# uc3906_charger_2.net
KiCad netlist of a schematic drawn in EAGLE
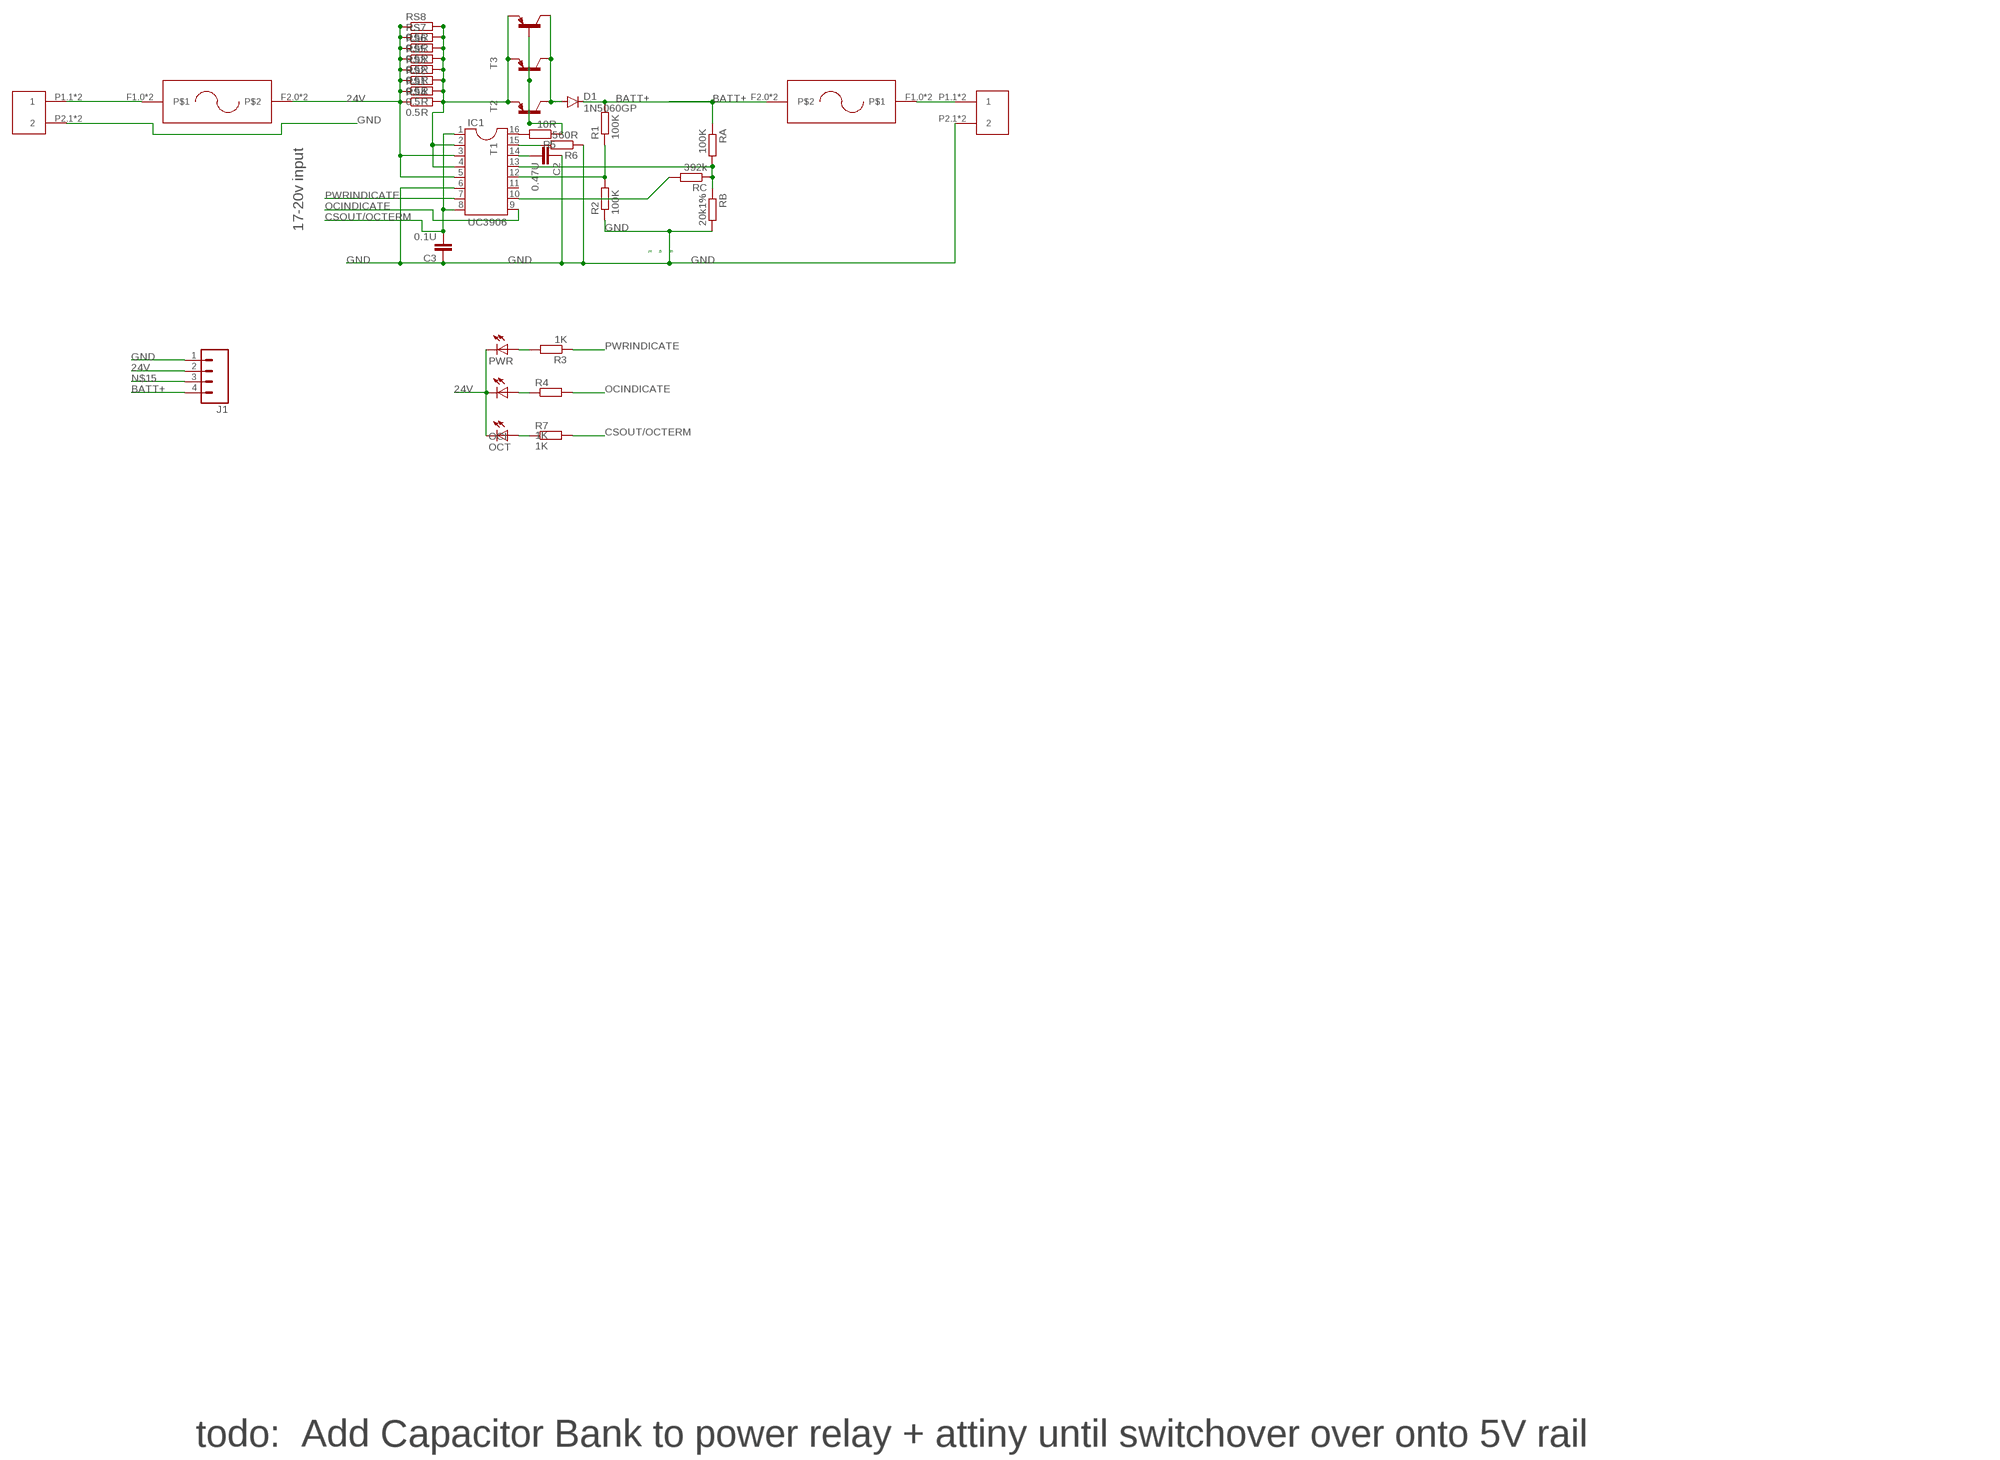
[diagram p0: schematic, sheet 1]

(export (version "E")
  (design (tool "Eeschema 10.0.6"))
  (components
    (comp (ref "BATT")
      (value "BARRIERTERMINAL")
      (footprint "eagle-import:BARRIERTERMINAL")
      (libsource (lib "eagle-import") (part "BARRIERTERMINAL"))
    )
    (comp (ref "C2")
      (value "0.47U")
      (footprint "eagle-import:C050-024X044")
      (libsource (lib "eagle-import") (part "C-EU050-024X044"))
    )
    (comp (ref "C3")
      (value "0.1U")
      (footprint "eagle-import:C050-024X044")
      (libsource (lib "eagle-import") (part "C-EU050-024X044"))
    )
    (comp (ref "D1")
      (value "1N5060GP")
      (footprint "eagle-import:DO15-12")
      (libsource (lib "eagle-import") (part "1N5060GP"))
    )
    (comp (ref "IC1")
      (value "UC3906")
      (footprint "eagle-import:DIL16")
      (libsource (lib "eagle-import") (part "DIL16"))
    )
    (comp (ref "J1")
      (value "CONN_04LONGPADS")
      (footprint "eagle-import:1X04_LONGPADS")
      (libsource (lib "eagle-import") (part "CONN_04LONGPADS"))
    )
    (comp (ref "OCI")
      (value "LED5MM")
      (footprint "eagle-import:LED5MM")
      (libsource (lib "eagle-import") (part "LED5MM"))
    )
    (comp (ref "OCT")
      (value "LED5MM")
      (footprint "eagle-import:LED5MM")
      (libsource (lib "eagle-import") (part "LED5MM"))
    )
    (comp (ref "POWERIN")
      (value "BARRIERTERMINAL")
      (footprint "eagle-import:BARRIERTERMINAL")
      (libsource (lib "eagle-import") (part "BARRIERTERMINAL"))
    )
    (comp (ref "PWR")
      (value "LED5MM")
      (footprint "eagle-import:LED5MM")
      (libsource (lib "eagle-import") (part "LED5MM"))
    )
    (comp (ref "R1")
      (value "100K")
      (footprint "eagle-import:0204_7")
      (libsource (lib "eagle-import") (part "R-EU_0204/7"))
    )
    (comp (ref "R2")
      (value "100K")
      (footprint "eagle-import:0204_7")
      (libsource (lib "eagle-import") (part "R-EU_0204/7"))
    )
    (comp (ref "R3")
      (value "1K")
      (footprint "eagle-import:0204_7")
      (libsource (lib "eagle-import") (part "R-EU_0204/7"))
    )
    (comp (ref "R4")
      (value "1K")
      (footprint "eagle-import:0204_7")
      (libsource (lib "eagle-import") (part "R-EU_0204/7"))
    )
    (comp (ref "R5")
      (value "10R")
      (footprint "eagle-import:0204_7")
      (libsource (lib "eagle-import") (part "R-EU_0204/7"))
    )
    (comp (ref "R6")
      (value "560R")
      (footprint "eagle-import:0204_7")
      (libsource (lib "eagle-import") (part "R-EU_0204/7"))
    )
    (comp (ref "R7")
      (value "1K")
      (footprint "eagle-import:0204_7")
      (libsource (lib "eagle-import") (part "R-EU_0204/7"))
    )
    (comp (ref "RA")
      (value "100K")
      (footprint "eagle-import:0204_7")
      (libsource (lib "eagle-import") (part "R-EU_0204/7"))
    )
    (comp (ref "RB")
      (value "20k1%")
      (footprint "eagle-import:0204_7")
      (libsource (lib "eagle-import") (part "R-EU_0204/7"))
    )
    (comp (ref "RC")
      (value "392k")
      (footprint "eagle-import:0204_7")
      (libsource (lib "eagle-import") (part "R-EU_0204/7"))
    )
    (comp (ref "RS1")
      (value "0.5R")
      (footprint "eagle-import:0411_15")
      (libsource (lib "eagle-import") (part "resistor_R-EU_0411/15"))
    )
    (comp (ref "RS2")
      (value "0.5R")
      (footprint "eagle-import:0411_15")
      (libsource (lib "eagle-import") (part "resistor_R-EU_0411/15"))
    )
    (comp (ref "RS3")
      (value "0.5R")
      (footprint "eagle-import:0411_15")
      (libsource (lib "eagle-import") (part "resistor_R-EU_0411/15"))
    )
    (comp (ref "RS4")
      (value "0.5R")
      (footprint "eagle-import:0411_15")
      (libsource (lib "eagle-import") (part "resistor_R-EU_0411/15"))
    )
    (comp (ref "RS5")
      (value "0.5R")
      (footprint "eagle-import:0411_15")
      (libsource (lib "eagle-import") (part "resistor_R-EU_0411/15"))
    )
    (comp (ref "RS6")
      (value "0.5R")
      (footprint "eagle-import:0411_15")
      (libsource (lib "eagle-import") (part "resistor_R-EU_0411/15"))
    )
    (comp (ref "RS7")
      (value "0.5R")
      (footprint "eagle-import:0411_15")
      (libsource (lib "eagle-import") (part "resistor_R-EU_0411/15"))
    )
    (comp (ref "RS8")
      (value "0.5R")
      (footprint "eagle-import:0411_15")
      (libsource (lib "eagle-import") (part "resistor_R-EU_0411/15"))
    )
    (comp (ref "T1")
      (value "TIP32C")
      (footprint "eagle-import:TO220")
      (libsource (lib "eagle-import") (part "TIP32C"))
    )
    (comp (ref "T2")
      (value "TIP32C")
      (footprint "eagle-import:TO220")
      (libsource (lib "eagle-import") (part "TIP32C"))
    )
    (comp (ref "T3")
      (value "TIP32C")
      (footprint "eagle-import:TO220")
      (libsource (lib "eagle-import") (part "TIP32C"))
    )
    (comp (ref "U$1")
      (value "18MMFUSEHOLDER")
      (footprint "eagle-import:18MMFUSEHOLDER")
      (libsource (lib "eagle-import") (part "18MMFUSEHOLDER"))
    )
    (comp (ref "U$2")
      (value "18MMFUSEHOLDER")
      (footprint "eagle-import:18MMFUSEHOLDER")
      (libsource (lib "eagle-import") (part "18MMFUSEHOLDER"))
    )
  )
  (nets
    (net (code "1") (name "/24V") (class "Default")
      (node (ref "IC1") (pin "3") (pinfunction "3_3") (pintype "passive"))
      (node (ref "IC1") (pin "5") (pinfunction "5_5") (pintype "passive"))
      (node (ref "J1") (pin "2") (pinfunction "2_2") (pintype "passive"))
      (node (ref "OCI") (pin "K") (pinfunction "C_K") (pintype "passive"))
      (node (ref "OCT") (pin "K") (pinfunction "C_K") (pintype "passive"))
      (node (ref "PWR") (pin "K") (pinfunction "C_K") (pintype "passive"))
      (node (ref "RS1") (pin "1") (pinfunction "1_1") (pintype "passive"))
      (node (ref "RS2") (pin "1") (pinfunction "1_1") (pintype "passive"))
      (node (ref "RS3") (pin "1") (pinfunction "1_1") (pintype "passive"))
      (node (ref "RS4") (pin "1") (pinfunction "1_1") (pintype "passive"))
      (node (ref "RS5") (pin "1") (pinfunction "1_1") (pintype "passive"))
      (node (ref "RS6") (pin "1") (pinfunction "1_1") (pintype "passive"))
      (node (ref "RS7") (pin "1") (pinfunction "1_1") (pintype "passive"))
      (node (ref "RS8") (pin "1") (pinfunction "1_1") (pintype "passive"))
      (node (ref "U$2") (pin "F2.0") (pinfunction "P$2_F2.0") (pintype "bidirectional"))
      (node (ref "U$2") (pin "F2.1") (pinfunction "P$2_F2.1") (pintype "bidirectional"))
    )
    (net (code "2") (name "/BATT+") (class "Default")
      (node (ref "D1") (pin "C") (pinfunction "C_C") (pintype "passive"))
      (node (ref "J1") (pin "4") (pinfunction "4_4") (pintype "passive"))
      (node (ref "R1") (pin "2") (pinfunction "2_2") (pintype "passive"))
      (node (ref "RA") (pin "1") (pinfunction "1_1") (pintype "passive"))
      (node (ref "U$1") (pin "F2.0") (pinfunction "P$2_F2.0") (pintype "bidirectional"))
      (node (ref "U$1") (pin "F2.1") (pinfunction "P$2_F2.1") (pintype "bidirectional"))
    )
    (net (code "3") (name "/CSOUT{slash}OCTERM") (class "Default")
      (node (ref "C3") (pin "2") (pinfunction "2_2") (pintype "passive"))
      (node (ref "IC1") (pin "1") (pinfunction "1_1") (pintype "passive"))
      (node (ref "IC1") (pin "8") (pinfunction "8_8") (pintype "passive"))
      (node (ref "R7") (pin "2") (pinfunction "2_2") (pintype "passive"))
    )
    (net (code "4") (name "/GND") (class "Default")
      (node (ref "BATT") (pin "P2.1") (pinfunction "2_P2.1") (pintype "bidirectional"))
      (node (ref "BATT") (pin "P2.2") (pinfunction "2_P2.2") (pintype "bidirectional"))
      (node (ref "C2") (pin "1") (pinfunction "1_1") (pintype "passive"))
      (node (ref "C3") (pin "1") (pinfunction "1_1") (pintype "passive"))
      (node (ref "IC1") (pin "6") (pinfunction "6_6") (pintype "passive"))
      (node (ref "J1") (pin "1") (pinfunction "1_1") (pintype "passive"))
      (node (ref "POWERIN") (pin "P2.1") (pinfunction "2_P2.1") (pintype "bidirectional"))
      (node (ref "POWERIN") (pin "P2.2") (pinfunction "2_P2.2") (pintype "bidirectional"))
      (node (ref "R2") (pin "1") (pinfunction "1_1") (pintype "passive"))
      (node (ref "R6") (pin "1") (pinfunction "1_1") (pintype "passive"))
      (node (ref "RB") (pin "2") (pinfunction "2_2") (pintype "passive"))
    )
    (net (code "5") (name "/N$15") (class "Default")
      (node (ref "D1") (pin "A") (pinfunction "A_A") (pintype "passive"))
      (node (ref "J1") (pin "3") (pinfunction "3_3") (pintype "passive"))
      (node (ref "T1") (pin "2") (pinfunction "C_2") (pintype "passive"))
      (node (ref "T2") (pin "2") (pinfunction "C_2") (pintype "passive"))
      (node (ref "T3") (pin "2") (pinfunction "C_2") (pintype "passive"))
    )
    (net (code "6") (name "/OCINDICATE") (class "Default")
      (node (ref "IC1") (pin "9") (pinfunction "9_9") (pintype "passive"))
      (node (ref "R4") (pin "2") (pinfunction "2_2") (pintype "passive"))
    )
    (net (code "7") (name "/PWRINDICATE") (class "Default")
      (node (ref "IC1") (pin "7") (pinfunction "7_7") (pintype "passive"))
      (node (ref "R3") (pin "1") (pinfunction "1_1") (pintype "passive"))
    )
    (net (code "8") (name "Net-(BATT-1-PadP1.1)") (class "Default")
      (node (ref "BATT") (pin "P1.1") (pinfunction "1_P1.1") (pintype "bidirectional"))
      (node (ref "BATT") (pin "P1.2") (pinfunction "1_P1.2") (pintype "bidirectional"))
      (node (ref "U$1") (pin "F1.0") (pinfunction "P$1_F1.0") (pintype "bidirectional"))
      (node (ref "U$1") (pin "F1.1") (pinfunction "P$1_F1.1") (pintype "bidirectional"))
    )
    (net (code "9") (name "Net-(C2-Pad2)") (class "Default")
      (node (ref "C2") (pin "2") (pinfunction "2_2") (pintype "passive"))
      (node (ref "IC1") (pin "14") (pinfunction "14_14") (pintype "passive"))
    )
    (net (code "10") (name "Net-(IC1-Pad10)") (class "Default")
      (node (ref "IC1") (pin "10") (pinfunction "10_10") (pintype "passive"))
      (node (ref "RC") (pin "2") (pinfunction "2_2") (pintype "passive"))
    )
    (net (code "11") (name "Net-(IC1-Pad12)") (class "Default")
      (node (ref "IC1") (pin "12") (pinfunction "12_12") (pintype "passive"))
      (node (ref "R1") (pin "1") (pinfunction "1_1") (pintype "passive"))
      (node (ref "R2") (pin "2") (pinfunction "2_2") (pintype "passive"))
    )
    (net (code "12") (name "Net-(IC1-Pad13)") (class "Default")
      (node (ref "IC1") (pin "13") (pinfunction "13_13") (pintype "passive"))
      (node (ref "RA") (pin "2") (pinfunction "2_2") (pintype "passive"))
      (node (ref "RB") (pin "1") (pinfunction "1_1") (pintype "passive"))
      (node (ref "RC") (pin "1") (pinfunction "1_1") (pintype "passive"))
    )
    (net (code "13") (name "Net-(IC1-Pad15)") (class "Default")
      (node (ref "IC1") (pin "15") (pinfunction "15_15") (pintype "passive"))
      (node (ref "R6") (pin "2") (pinfunction "2_2") (pintype "passive"))
    )
    (net (code "14") (name "Net-(IC1-Pad16)") (class "Default")
      (node (ref "IC1") (pin "16") (pinfunction "16_16") (pintype "passive"))
      (node (ref "R5") (pin "2") (pinfunction "2_2") (pintype "passive"))
    )
    (net (code "15") (name "Net-(OCI-PadA)") (class "Default")
      (node (ref "OCI") (pin "A") (pinfunction "A_A") (pintype "passive"))
      (node (ref "R4") (pin "1") (pinfunction "1_1") (pintype "passive"))
    )
    (net (code "16") (name "Net-(OCT-PadA)") (class "Default")
      (node (ref "OCT") (pin "A") (pinfunction "A_A") (pintype "passive"))
      (node (ref "R7") (pin "1") (pinfunction "1_1") (pintype "passive"))
    )
    (net (code "17") (name "Net-(POWERIN-1-PadP1.1)") (class "Default")
      (node (ref "POWERIN") (pin "P1.1") (pinfunction "1_P1.1") (pintype "bidirectional"))
      (node (ref "POWERIN") (pin "P1.2") (pinfunction "1_P1.2") (pintype "bidirectional"))
      (node (ref "U$2") (pin "F1.0") (pinfunction "P$1_F1.0") (pintype "bidirectional"))
      (node (ref "U$2") (pin "F1.1") (pinfunction "P$1_F1.1") (pintype "bidirectional"))
    )
    (net (code "18") (name "Net-(PWR-PadA)") (class "Default")
      (node (ref "PWR") (pin "A") (pinfunction "A_A") (pintype "passive"))
      (node (ref "R3") (pin "2") (pinfunction "2_2") (pintype "passive"))
    )
    (net (code "19") (name "Net-(T1-B)") (class "Default")
      (node (ref "R5") (pin "1") (pinfunction "1_1") (pintype "passive"))
      (node (ref "T1") (pin "1") (pinfunction "B_1") (pintype "passive"))
      (node (ref "T2") (pin "1") (pinfunction "B_1") (pintype "passive"))
      (node (ref "T3") (pin "1") (pinfunction "B_1") (pintype "passive"))
    )
    (net (code "20") (name "Net-(T1-E)") (class "Default")
      (node (ref "IC1") (pin "2") (pinfunction "2_2") (pintype "passive"))
      (node (ref "IC1") (pin "4") (pinfunction "4_4") (pintype "passive"))
      (node (ref "RS1") (pin "2") (pinfunction "2_2") (pintype "passive"))
      (node (ref "RS2") (pin "2") (pinfunction "2_2") (pintype "passive"))
      (node (ref "RS3") (pin "2") (pinfunction "2_2") (pintype "passive"))
      (node (ref "RS4") (pin "2") (pinfunction "2_2") (pintype "passive"))
      (node (ref "RS5") (pin "2") (pinfunction "2_2") (pintype "passive"))
      (node (ref "RS6") (pin "2") (pinfunction "2_2") (pintype "passive"))
      (node (ref "RS7") (pin "2") (pinfunction "2_2") (pintype "passive"))
      (node (ref "RS8") (pin "2") (pinfunction "2_2") (pintype "passive"))
      (node (ref "T1") (pin "3") (pinfunction "E_3") (pintype "passive"))
      (node (ref "T2") (pin "3") (pinfunction "E_3") (pintype "passive"))
      (node (ref "T3") (pin "3") (pinfunction "E_3") (pintype "passive"))
    )
    (net (code "21") (name "unconnected-(IC1-Pad11)") (class "Default")
      (node (ref "IC1") (pin "11") (pinfunction "11_11") (pintype "passive"))
    )
  )
)
